# Sheet1.net
KiCad netlist of a schematic drawn in Altium Designer
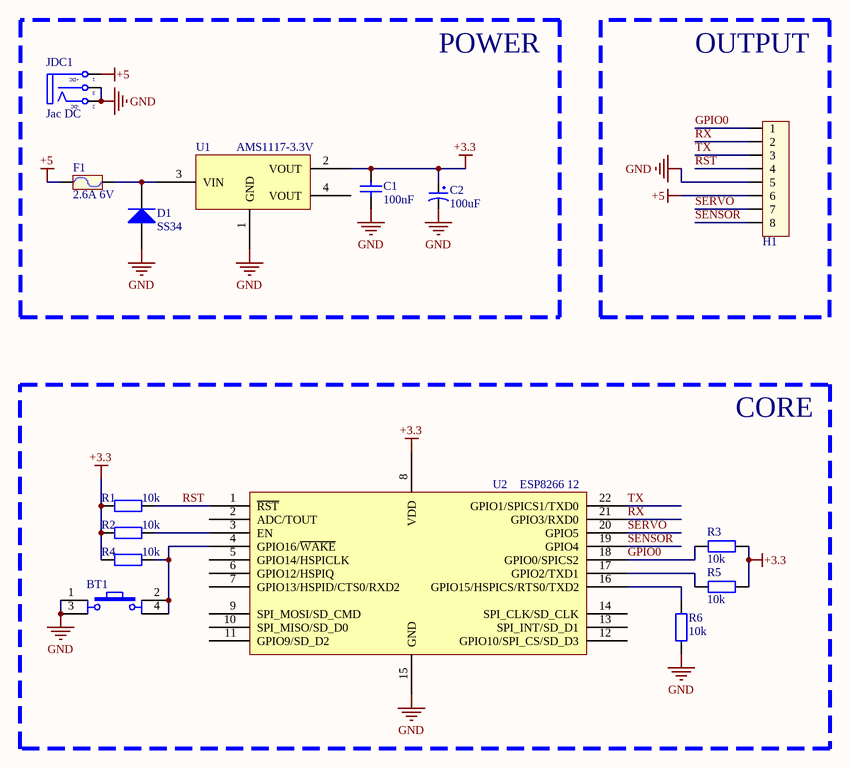
[diagram p0: Sheet1.SchDoc]

(export (version "E")
  (design (tool "Eeschema 10.0.6"))
  (components
    (comp (ref "BT1")
      (value "Nut Nhan 4 Chan SMD 6x6")
      (footprint "Nut Nhan 4 Chan SMD 6x6")
      (description "Nut Nhan 4 Chan 6.2x6.2x3.5")
      (libsource (lib "Altium_Lib_by_KhueNguyenCreator") (part "Nut Nhan 4 Chan SMD 6x6"))
    )
    (comp (ref "C1")
      (value "100nF")
      (footprint "tu 0805")
      (description "Dán")
      (libsource (lib "Altium_Lib_by_KhueNguyenCreator") (part "Tu 0805 221 50V"))
    )
    (comp (ref "C2")
      (value "100uF")
      (footprint "tu tantalum smd3528")
      (description "Tu Tantalum SMD3528")
      (libsource (lib "Altium_Lib_by_KhueNguyenCreator") (part "Tu tantalum 100uF 6.3V SMD3528"))
    )
    (comp (ref "D1")
      (value "SS34")
      (footprint "DIODE SMA")
      (description "Dán")
      (libsource (lib "Altium_Lib_by_KhueNguyenCreator") (part "Diode SS34 ( 1N5822 )"))
    )
    (comp (ref "F1")
      (value "2.6A 6V")
      (footprint "Cau chi tu phuc hoi 2A 24V SMD1812")
      (libsource (lib "Altium_Lib_by_KhueNguyenCreator") (part "Cau chi tu phuc hoi 2A 24V SMD1812"))
    )
    (comp (ref "H1")
      (value "Header 8P 2.54 Duc Thang")
      (footprint "XH2.54M-8")
      (description "Cắm")
      (libsource (lib "Altium_Lib_by_KhueNguyenCreator") (part "Header 8P 2.54 Duc Thang"))
    )
    (comp (ref "JDC1")
      (value "Jac DC")
      (footprint "DC0")
      (description "Jac DC input")
      (libsource (lib "LIBRARY1") (part "DCIN"))
    )
    (comp (ref "R1")
      (value "10k")
      (footprint "tro smd 0805")
      (description "Dán")
      (libsource (lib "Altium_Lib_by_KhueNguyenCreator") (part "Tro 0805 5% 12k"))
    )
    (comp (ref "R2")
      (value "10k")
      (footprint "tro smd 0805")
      (description "Dán")
      (libsource (lib "Altium_Lib_by_KhueNguyenCreator") (part "Tro 0805 5% 12k"))
    )
    (comp (ref "R3")
      (value "10k")
      (footprint "tro smd 0805")
      (description "Dán")
      (libsource (lib "Altium_Lib_by_KhueNguyenCreator") (part "Tro 0805 5% 12k"))
    )
    (comp (ref "R4")
      (value "10k")
      (footprint "tro smd 0805")
      (description "Dán")
      (libsource (lib "Altium_Lib_by_KhueNguyenCreator") (part "Tro 0805 5% 12k"))
    )
    (comp (ref "R5")
      (value "10k")
      (footprint "tro smd 0805")
      (description "Dán")
      (libsource (lib "Altium_Lib_by_KhueNguyenCreator") (part "Tro 0805 5% 12k"))
    )
    (comp (ref "R6")
      (value "10k")
      (footprint "tro smd 0805")
      (description "Dán")
      (libsource (lib "Altium_Lib_by_KhueNguyenCreator") (part "Tro 0805 5% 12k"))
    )
    (comp (ref "U1")
      (value "AMS1117-3.3V")
      (footprint "SOT223")
      (description "Dán")
      (libsource (lib "Altium_Lib_by_KhueNguyenCreator") (part "AMS1117 SMD"))
    )
    (comp (ref "U2")
      (value "ESP8266 12")
      (footprint "ESP8266 12")
      (description "ESP8266 12 22 Pin")
      (libsource (lib "Altium_Lib_by_KhueNguyenCreator") (part "ESP8266 12"))
    )
  )
  (nets
    (net (code "1") (name "+3.3") (class "Default")
      (node (ref "C1") (pin "1") (pinfunction "1_1") (pintype "passive"))
      (node (ref "C2") (pin "1") (pinfunction "1_1") (pintype "passive"))
      (node (ref "R1") (pin "2") (pinfunction "2_2") (pintype "passive"))
      (node (ref "R2") (pin "2") (pinfunction "2_2") (pintype "passive"))
      (node (ref "R3") (pin "2") (pinfunction "2_2") (pintype "passive"))
      (node (ref "R4") (pin "2") (pinfunction "2_2") (pintype "passive"))
      (node (ref "R5") (pin "2") (pinfunction "2_2") (pintype "passive"))
      (node (ref "U1") (pin "2") (pinfunction "VOUT_2") (pintype "passive"))
      (node (ref "U2") (pin "8") (pinfunction "VDD_8") (pintype "passive"))
    )
    (net (code "2") (name "+5") (class "Default")
      (node (ref "F1") (pin "2") (pinfunction "2_2") (pintype "passive"))
      (node (ref "H1") (pin "6") (pinfunction "6_6") (pintype "passive"))
      (node (ref "JDC1") (pin "1") (pinfunction "T_1") (pintype "passive"))
    )
    (net (code "4") (name "/GPIO0") (class "Default")
      (node (ref "H1") (pin "1") (pinfunction "1_1") (pintype "passive"))
      (node (ref "R3") (pin "1") (pinfunction "1_1") (pintype "passive"))
      (node (ref "U2") (pin "18") (pinfunction "GPIO0/SPICS2_18") (pintype "passive"))
    )
    (net (code "5") (name "/RST") (class "Default")
      (node (ref "H1") (pin "4") (pinfunction "4_4") (pintype "passive"))
      (node (ref "R1") (pin "1") (pinfunction "1_1") (pintype "passive"))
      (node (ref "U2") (pin "1") (pinfunction "~{RST}_1") (pintype "passive"))
    )
    (net (code "6") (name "/RX") (class "Default")
      (node (ref "H1") (pin "2") (pinfunction "2_2") (pintype "passive"))
      (node (ref "U2") (pin "21") (pinfunction "GPIO3/RXD0_21") (pintype "passive"))
    )
    (net (code "7") (name "/SENSOR") (class "Default")
      (node (ref "H1") (pin "8") (pinfunction "8_8") (pintype "passive"))
      (node (ref "U2") (pin "19") (pinfunction "GPIO4_19") (pintype "passive"))
    )
    (net (code "8") (name "/SERVO") (class "Default")
      (node (ref "H1") (pin "7") (pinfunction "7_7") (pintype "passive"))
      (node (ref "U2") (pin "20") (pinfunction "GPIO5_20") (pintype "passive"))
    )
    (net (code "9") (name "/TX") (class "Default")
      (node (ref "H1") (pin "3") (pinfunction "3_3") (pintype "passive"))
      (node (ref "U2") (pin "22") (pinfunction "GPIO1/SPICS1/TXD0_22") (pintype "passive"))
    )
    (net (code "10") (name "GND") (class "Default")
      (node (ref "BT1") (pin "1") (pintype "passive"))
      (node (ref "BT1") (pin "3") (pintype "passive"))
      (node (ref "C1") (pin "2") (pinfunction "2_2") (pintype "passive"))
      (node (ref "C2") (pin "2") (pinfunction "2_2") (pintype "passive"))
      (node (ref "D1") (pin "1") (pinfunction "A_1") (pintype "passive"))
      (node (ref "H1") (pin "5") (pinfunction "5_5") (pintype "passive"))
      (node (ref "JDC1") (pin "2") (pinfunction "TN_2") (pintype "passive"))
      (node (ref "JDC1") (pin "3") (pinfunction "S_3") (pintype "power_in"))
      (node (ref "R6") (pin "1") (pinfunction "1_1") (pintype "passive"))
      (node (ref "U1") (pin "1") (pinfunction "GND_1") (pintype "passive"))
      (node (ref "U2") (pin "15") (pinfunction "GND_15") (pintype "passive"))
    )
    (net (code "11") (name "Net-(D1-K)") (class "Default")
      (node (ref "D1") (pin "2") (pinfunction "K_2") (pintype "passive"))
      (node (ref "F1") (pin "1") (pinfunction "1_1") (pintype "passive"))
      (node (ref "U1") (pin "3") (pinfunction "VIN_3") (pintype "passive"))
    )
    (net (code "12") (name "Net-(U2-EN)") (class "Default")
      (node (ref "R2") (pin "1") (pinfunction "1_1") (pintype "passive"))
      (node (ref "U2") (pin "3") (pinfunction "EN_3") (pintype "passive"))
    )
    (net (code "13") (name "Net-(U2-GPIO2{slash}TXD1)") (class "Default")
      (node (ref "R5") (pin "1") (pinfunction "1_1") (pintype "passive"))
      (node (ref "U2") (pin "17") (pinfunction "GPIO2/TXD1_17") (pintype "passive"))
    )
    (net (code "14") (name "Net-(U2-GPIO15{slash}HSPICS{slash}RTS0{slash}TXD2)") (class "Default")
      (node (ref "R6") (pin "2") (pinfunction "2_2") (pintype "passive"))
      (node (ref "U2") (pin "16") (pinfunction "GPIO15/HSPICS/RTS0/TXD2_16") (pintype "passive"))
    )
    (net (code "15") (name "Net-(U2-GPIO16{slash}~{WAKE})") (class "Default")
      (node (ref "BT1") (pin "2") (pintype "passive"))
      (node (ref "BT1") (pin "4") (pintype "passive"))
      (node (ref "R4") (pin "1") (pinfunction "1_1") (pintype "passive"))
      (node (ref "U2") (pin "4") (pinfunction "GPIO16/~{WAKE}_4") (pintype "passive"))
    )
    (net (code "16") (name "unconnected-(U1-VOUT-Pad4)") (class "Default")
      (node (ref "U1") (pin "4") (pinfunction "VOUT_4") (pintype "passive"))
    )
    (net (code "17") (name "unconnected-(U2-ADC{slash}TOUT-Pad2)") (class "Default")
      (node (ref "U2") (pin "2") (pinfunction "ADC/TOUT_2") (pintype "passive"))
    )
    (net (code "18") (name "unconnected-(U2-GPIO9{slash}SD_D2-Pad11)") (class "Default")
      (node (ref "U2") (pin "11") (pinfunction "GPIO9/SD_D2_11") (pintype "passive"))
    )
    (net (code "19") (name "unconnected-(U2-GPIO10{slash}SPI_CS{slash}SD_D3-Pad12)") (class "Default")
      (node (ref "U2") (pin "12") (pinfunction "GPIO10/SPI_CS/SD_D3_12") (pintype "passive"))
    )
    (net (code "20") (name "unconnected-(U2-GPIO12{slash}HSPIQ-Pad6)") (class "Default")
      (node (ref "U2") (pin "6") (pinfunction "GPIO12/HSPIQ_6") (pintype "passive"))
    )
    (net (code "21") (name "unconnected-(U2-GPIO13{slash}HSPID{slash}CTS0{slash}RXD2-Pad7)") (class "Default")
      (node (ref "U2") (pin "7") (pinfunction "GPIO13/HSPID/CTS0/RXD2_7") (pintype "passive"))
    )
    (net (code "22") (name "unconnected-(U2-GPIO14{slash}HSPICLK-Pad5)") (class "Default")
      (node (ref "U2") (pin "5") (pinfunction "GPIO14/HSPICLK_5") (pintype "passive"))
    )
    (net (code "23") (name "unconnected-(U2-SPI_CLK{slash}SD_CLK-Pad14)") (class "Default")
      (node (ref "U2") (pin "14") (pinfunction "SPI_CLK/SD_CLK_14") (pintype "passive"))
    )
    (net (code "24") (name "unconnected-(U2-SPI_INT{slash}SD_D1-Pad13)") (class "Default")
      (node (ref "U2") (pin "13") (pinfunction "SPI_INT/SD_D1_13") (pintype "passive"))
    )
    (net (code "25") (name "unconnected-(U2-SPI_MISO{slash}SD_D0-Pad10)") (class "Default")
      (node (ref "U2") (pin "10") (pinfunction "SPI_MISO/SD_D0_10") (pintype "passive"))
    )
    (net (code "26") (name "unconnected-(U2-SPI_MOSI{slash}SD_CMD-Pad9)") (class "Default")
      (node (ref "U2") (pin "9") (pinfunction "SPI_MOSI/SD_CMD_9") (pintype "passive"))
    )
  )
)
